# OTII-Breakout.net
KiCad netlist of a schematic drawn in EAGLE
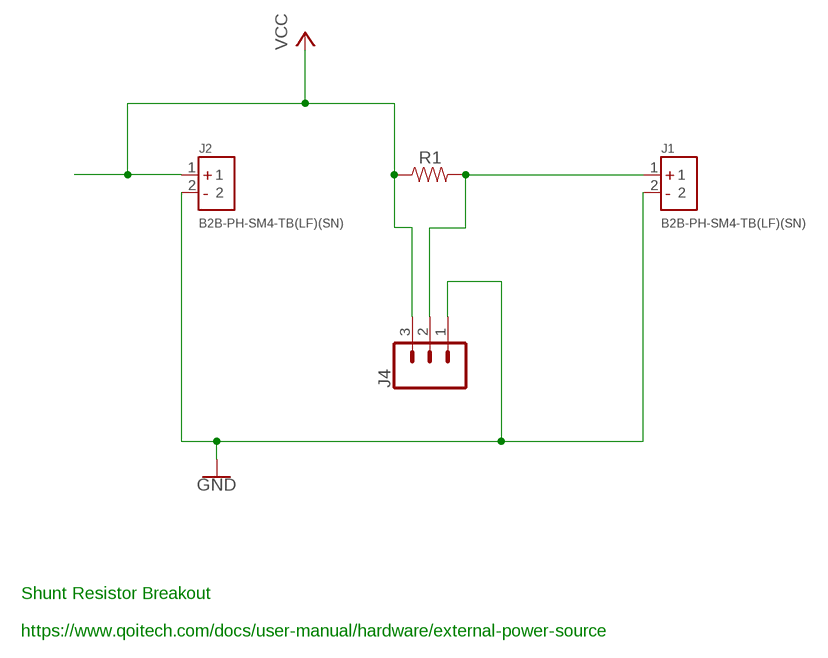
[diagram p0: schematic, sheet 1]

(export (version "E")
  (design (tool "Eeschema 10.0.6"))
  (components
    (comp (ref "J1")
      (value "B2B-PH-SM4-TB(LF)(SN)")
      (footprint "eagle-import:JST_B2B-PH-SM4-TB(LF)(SN)")
      (fields (field (name "DIGI-KEY_PART_NUMBER") "455-1734-1-ND") (field (name "MF") "JST Sales"))
      (libsource (lib "eagle-import") (part "B2B-PH-SM4-TB(LF)(SN)"))
    )
    (comp (ref "J2")
      (value "B2B-PH-SM4-TB(LF)(SN)")
      (footprint "eagle-import:JST_B2B-PH-SM4-TB(LF)(SN)")
      (fields (field (name "DIGI-KEY_PART_NUMBER") "455-1734-1-ND") (field (name "MF") "JST Sales"))
      (libsource (lib "eagle-import") (part "B2B-PH-SM4-TB(LF)(SN)"))
    )
    (comp (ref "J4")
      (value "CONN_03")
      (footprint "eagle-import:1X03")
      (libsource (lib "eagle-import") (part "CONN_03"))
    )
    (comp (ref "R1")
      (value "RESISTOR-MF-0805")
      (footprint "eagle-import:0805")
      (libsource (lib "eagle-import") (part "RESISTOR-MF-0805"))
    )
  )
  (nets
    (net (code "1") (name "GND") (class "Default")
      (node (ref "J1") (pin "2") (pinfunction "2_2") (pintype "passive"))
      (node (ref "J2") (pin "2") (pinfunction "2_2") (pintype "passive"))
      (node (ref "J4") (pin "1") (pinfunction "1_1") (pintype "passive"))
    )
    (net (code "2") (name "Net-(J1-Pad1)") (class "Default")
      (node (ref "J1") (pin "1") (pinfunction "1_1") (pintype "passive"))
      (node (ref "J4") (pin "2") (pinfunction "2_2") (pintype "passive"))
      (node (ref "R1") (pin "2") (pinfunction "2_2") (pintype "passive"))
    )
    (net (code "3") (name "VCC") (class "Default")
      (node (ref "J2") (pin "1") (pinfunction "1_1") (pintype "passive"))
      (node (ref "J4") (pin "3") (pinfunction "3_3") (pintype "passive"))
      (node (ref "R1") (pin "1") (pinfunction "1_1") (pintype "passive"))
    )
  )
)
